# Zentrale.net
KiCad netlist of a schematic drawn in EAGLE
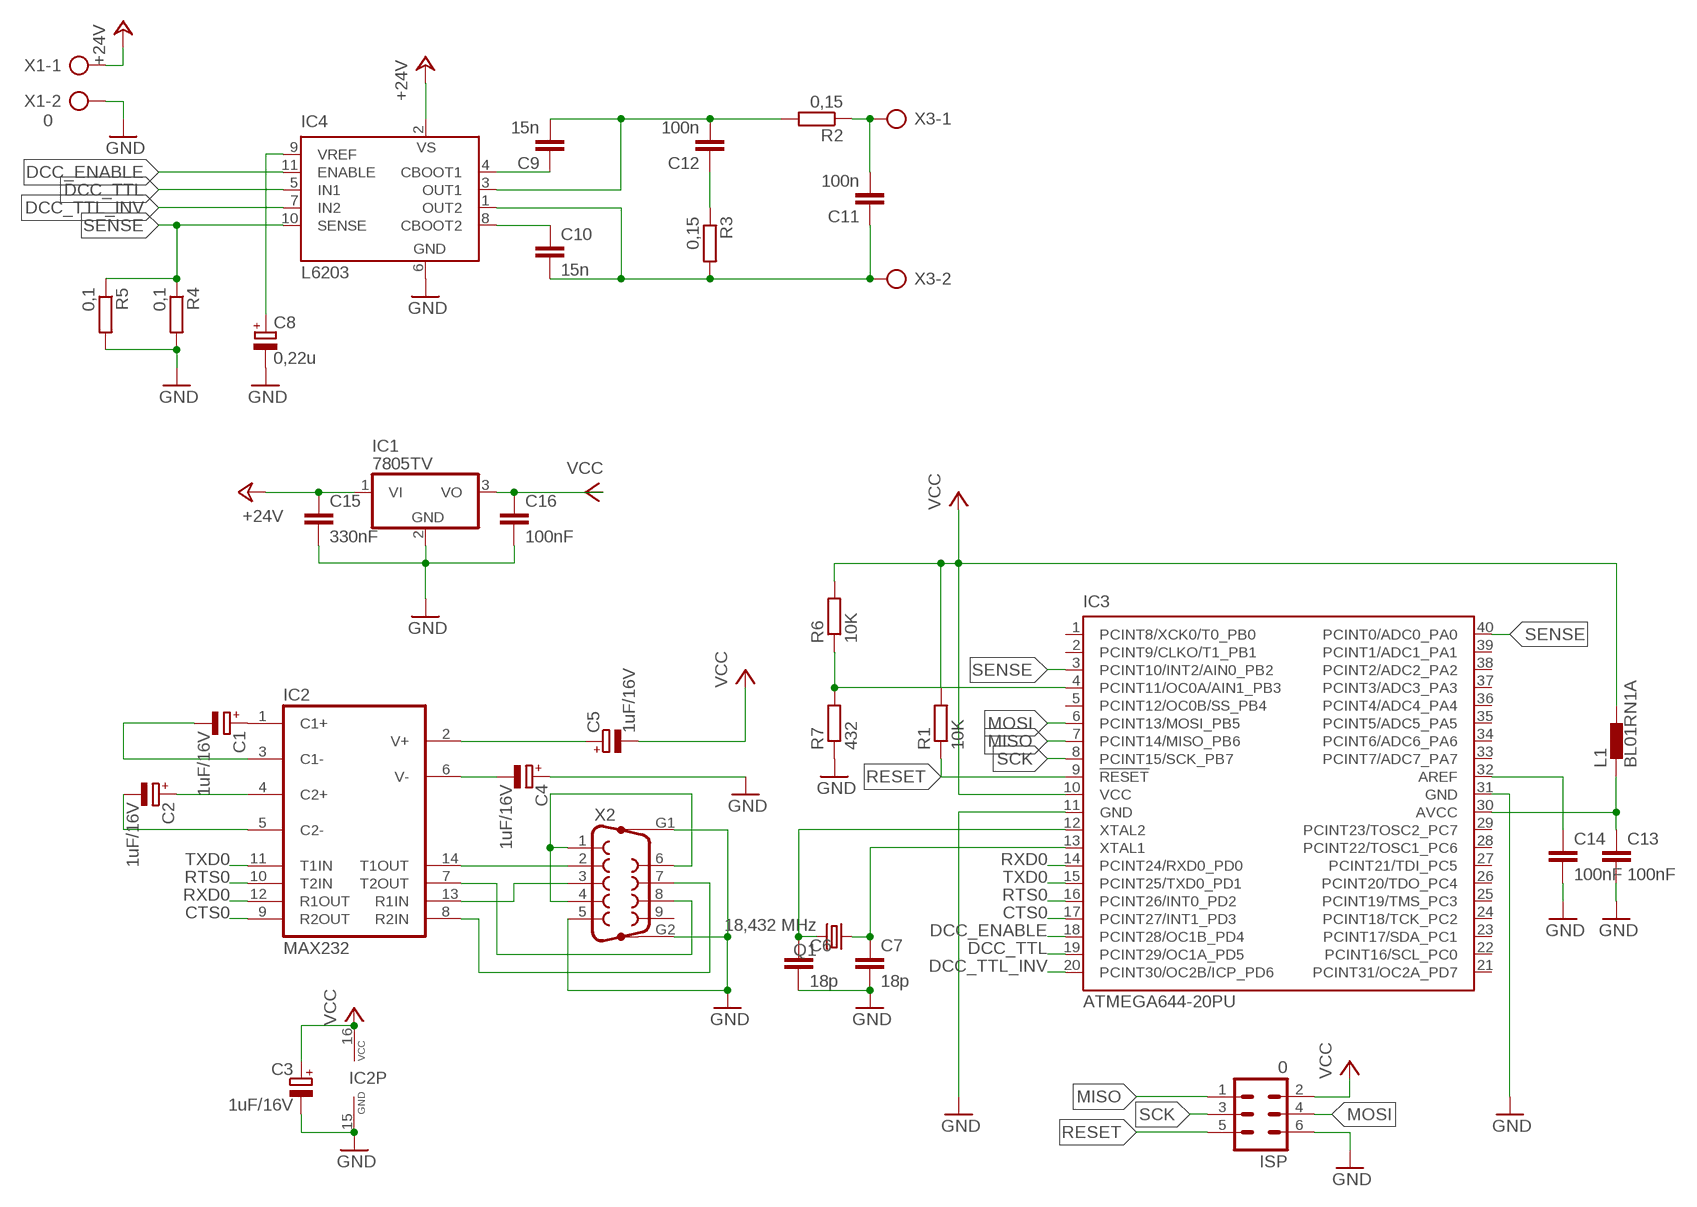
[diagram p0: schematic, sheet 1]

(export (version "E")
  (design (tool "Eeschema 10.0.6"))
  (components
    (comp (ref "C1")
      (value "1uF/16V")
      (footprint "eagle-import:TT2D5")
      (libsource (lib "eagle-import") (part "CPOL-EUTT2D5"))
    )
    (comp (ref "C2")
      (value "1uF/16V")
      (footprint "eagle-import:TT2D5")
      (libsource (lib "eagle-import") (part "CPOL-EUTT2D5"))
    )
    (comp (ref "C3")
      (value "1uF/16V")
      (footprint "eagle-import:TT2D5")
      (libsource (lib "eagle-import") (part "CPOL-EUTT2D5"))
    )
    (comp (ref "C4")
      (value "1uF/16V")
      (footprint "eagle-import:TT2D5")
      (libsource (lib "eagle-import") (part "CPOL-EUTT2D5"))
    )
    (comp (ref "C5")
      (value "1uF/16V")
      (footprint "eagle-import:TT2D5")
      (libsource (lib "eagle-import") (part "CPOL-EUTT2D5"))
    )
    (comp (ref "C6")
      (value "18p")
      (footprint "eagle-import:C025-025X050")
      (libsource (lib "eagle-import") (part "C-EU025-025X050"))
    )
    (comp (ref "C7")
      (value "18p")
      (footprint "eagle-import:C025-025X050")
      (libsource (lib "eagle-import") (part "C-EU025-025X050"))
    )
    (comp (ref "C8")
      (value "0,22u")
      (footprint "eagle-import:TT2D5")
      (libsource (lib "eagle-import") (part "CPOL-EUTT2D5"))
    )
    (comp (ref "C9")
      (value "15n")
      (footprint "eagle-import:C025-025X050")
      (libsource (lib "eagle-import") (part "C-EU025-025X050"))
    )
    (comp (ref "C10")
      (value "15n")
      (footprint "eagle-import:C025-025X050")
      (libsource (lib "eagle-import") (part "C-EU025-025X050"))
    )
    (comp (ref "C11")
      (value "100n")
      (footprint "eagle-import:C025-025X050")
      (libsource (lib "eagle-import") (part "C-EU025-025X050"))
    )
    (comp (ref "C12")
      (value "100n")
      (footprint "eagle-import:C025-025X050")
      (libsource (lib "eagle-import") (part "C-EU025-025X050"))
    )
    (comp (ref "C13")
      (value "100nF")
      (footprint "eagle-import:C025-025X050")
      (libsource (lib "eagle-import") (part "C-EU025-025X050"))
    )
    (comp (ref "C14")
      (value "100nF")
      (footprint "eagle-import:C025-025X050")
      (libsource (lib "eagle-import") (part "C-EU025-025X050"))
    )
    (comp (ref "C15")
      (value "330nF")
      (footprint "eagle-import:C025-025X050")
      (libsource (lib "eagle-import") (part "C-EU025-025X050"))
    )
    (comp (ref "C16")
      (value "100nF")
      (footprint "eagle-import:C025-025X050")
      (libsource (lib "eagle-import") (part "C-EU025-025X050"))
    )
    (comp (ref "IC1")
      (value "7805TV")
      (footprint "eagle-import:TO220V")
      (libsource (lib "eagle-import") (part "78TV05"))
    )
    (comp (ref "IC2")
      (value "MAX232")
      (footprint "eagle-import:DIL16")
      (fields (field (name "MF") "MAXIM") (field (name "MPN") "MAX232ACPE+"))
      (libsource (lib "eagle-import") (part "MAX232"))
    )
    (comp (ref "IC3")
      (value "ATMEGA644-20PU")
      (footprint "eagle-import:DIL40")
      (libsource (lib "eagle-import") (part "ATMEGA644-PU20"))
    )
    (comp (ref "IC4")
      (value "L6203")
      (footprint "eagle-import:MULTIWATT-11")
      (libsource (lib "eagle-import") (part "L6203"))
    )
    (comp (ref "ISP")
      (value "0")
      (footprint "eagle-import:ML6")
      (libsource (lib "eagle-import") (part "ML6"))
    )
    (comp (ref "L1")
      (value "BL01RN1A")
      (footprint "eagle-import:BL01RN1A")
      (libsource (lib "eagle-import") (part "BL01RN1A"))
    )
    (comp (ref "Q1")
      (value "18,432 MHz")
      (footprint "eagle-import:HC18U-V")
      (libsource (lib "eagle-import") (part "CRYSTALHC18U-V"))
    )
    (comp (ref "R1")
      (value "10K")
      (footprint "eagle-import:0204_5")
      (libsource (lib "eagle-import") (part "R-EU_0204/5"))
    )
    (comp (ref "R2")
      (value "0,15")
      (footprint "eagle-import:0204_5")
      (libsource (lib "eagle-import") (part "R-EU_0204/5"))
    )
    (comp (ref "R3")
      (value "0,15")
      (footprint "eagle-import:0204_5")
      (libsource (lib "eagle-import") (part "R-EU_0204/5"))
    )
    (comp (ref "R4")
      (value "0,1")
      (footprint "eagle-import:0204_5")
      (libsource (lib "eagle-import") (part "R-EU_0204/5"))
    )
    (comp (ref "R5")
      (value "0,1")
      (footprint "eagle-import:0204_5")
      (libsource (lib "eagle-import") (part "R-EU_0204/5"))
    )
    (comp (ref "R6")
      (value "10K")
      (footprint "eagle-import:0204_5")
      (libsource (lib "eagle-import") (part "R-EU_0204/5"))
    )
    (comp (ref "R7")
      (value "432")
      (footprint "eagle-import:0204_5")
      (libsource (lib "eagle-import") (part "R-EU_0204/5"))
    )
    (comp (ref "X1")
      (value "0")
      (footprint "eagle-import:AK500_2")
      (libsource (lib "eagle-import") (part "AK500/2"))
    )
    (comp (ref "X2")
      (value "F09HP")
      (footprint "eagle-import:F09HP")
      (libsource (lib "eagle-import") (part "F09HP"))
    )
    (comp (ref "X3")
      (value "AK500/2")
      (footprint "eagle-import:AK500_2")
      (libsource (lib "eagle-import") (part "AK500/2"))
    )
  )
  (nets
    (net (code "1") (name "+24V") (class "Default")
      (node (ref "C15") (pin "1") (pinfunction "1_1") (pintype "passive"))
      (node (ref "IC1") (pin "1") (pinfunction "VI_1") (pintype "input"))
      (node (ref "IC4") (pin "2") (pinfunction "VS_2") (pintype "power_in"))
      (node (ref "X1") (pin "1") (pinfunction "KL_1") (pintype "passive"))
    )
    (net (code "2") (name "/CTS0") (class "Default")
      (node (ref "IC2") (pin "9") (pinfunction "R2OUT_9") (pintype "output"))
      (node (ref "IC3") (pin "17") (pinfunction "PCINT27/INT1_PD3_17") (pintype "bidirectional"))
    )
    (net (code "3") (name "/RTS0") (class "Default")
      (node (ref "IC2") (pin "10") (pinfunction "T2IN_10") (pintype "input"))
      (node (ref "IC3") (pin "16") (pinfunction "PCINT26/INT0_PD2_16") (pintype "bidirectional"))
    )
    (net (code "4") (name "/RXD0") (class "Default")
      (node (ref "IC2") (pin "12") (pinfunction "R1OUT_12") (pintype "output"))
      (node (ref "IC3") (pin "14") (pinfunction "PCINT24/RXD0_PD0_14") (pintype "bidirectional"))
    )
    (net (code "5") (name "/TXD0") (class "Default")
      (node (ref "IC2") (pin "11") (pinfunction "T1IN_11") (pintype "input"))
      (node (ref "IC3") (pin "15") (pinfunction "PCINT25/TXD0_PD1_15") (pintype "bidirectional"))
    )
    (net (code "6") (name "DCC_ENABLE") (class "Default")
      (node (ref "IC3") (pin "18") (pinfunction "PCINT28/OC1B_PD4_18") (pintype "bidirectional"))
      (node (ref "IC4") (pin "11") (pinfunction "ENABLE_11") (pintype "input"))
    )
    (net (code "7") (name "DCC_TTL") (class "Default")
      (node (ref "IC3") (pin "19") (pinfunction "PCINT29/OC1A_PD5_19") (pintype "bidirectional"))
      (node (ref "IC4") (pin "5") (pinfunction "IN1_5") (pintype "input"))
    )
    (net (code "8") (name "DCC_TTL_INV") (class "Default")
      (node (ref "IC3") (pin "20") (pinfunction "PCINT30/OC2B/ICP_PD6_20") (pintype "bidirectional"))
      (node (ref "IC4") (pin "7") (pinfunction "IN2_7") (pintype "input"))
    )
    (net (code "9") (name "GND") (class "Default")
      (node (ref "C13") (pin "2") (pinfunction "2_2") (pintype "passive"))
      (node (ref "C14") (pin "2") (pinfunction "2_2") (pintype "passive"))
      (node (ref "C15") (pin "2") (pinfunction "2_2") (pintype "passive"))
      (node (ref "C16") (pin "2") (pinfunction "2_2") (pintype "passive"))
      (node (ref "C3") (pin "-") (pinfunction "-_-") (pintype "passive"))
      (node (ref "C4") (pin "+") (pinfunction "+_+") (pintype "passive"))
      (node (ref "C6") (pin "2") (pinfunction "2_2") (pintype "passive"))
      (node (ref "C7") (pin "2") (pinfunction "2_2") (pintype "passive"))
      (node (ref "C8") (pin "-") (pinfunction "-_-") (pintype "passive"))
      (node (ref "IC1") (pin "2") (pinfunction "GND_2") (pintype "passive"))
      (node (ref "IC2") (pin "15") (pinfunction "GND_15") (pintype "power_in"))
      (node (ref "IC3") (pin "11") (pinfunction "GND_11") (pintype "power_in"))
      (node (ref "IC3") (pin "31") (pinfunction "GND_31") (pintype "power_in"))
      (node (ref "IC4") (pin "6") (pinfunction "GND_6") (pintype "power_in"))
      (node (ref "ISP") (pin "6") (pinfunction "6_6") (pintype "passive"))
      (node (ref "R4") (pin "2") (pinfunction "2_2") (pintype "passive"))
      (node (ref "R5") (pin "2") (pinfunction "2_2") (pintype "passive"))
      (node (ref "R7") (pin "1") (pinfunction "1_1") (pintype "passive"))
      (node (ref "X1") (pin "2") (pinfunction "KL_2") (pintype "passive"))
      (node (ref "X2") (pin "5") (pinfunction "5_5") (pintype "passive"))
      (node (ref "X2") (pin "G1") (pinfunction "G1_G1") (pintype "passive"))
      (node (ref "X2") (pin "G2") (pinfunction "G2_G2") (pintype "passive"))
    )
    (net (code "10") (name "MISO") (class "Default")
      (node (ref "IC3") (pin "7") (pinfunction "PCINT14/MISO_PB6_7") (pintype "bidirectional"))
      (node (ref "ISP") (pin "1") (pinfunction "1_1") (pintype "passive"))
    )
    (net (code "11") (name "MOSI") (class "Default")
      (node (ref "IC3") (pin "6") (pinfunction "PCINT13/MOSI_PB5_6") (pintype "bidirectional"))
      (node (ref "ISP") (pin "4") (pinfunction "4_4") (pintype "passive"))
    )
    (net (code "12") (name "Net-(C12-Pad1)") (class "Default")
      (node (ref "C12") (pin "1") (pinfunction "1_1") (pintype "passive"))
      (node (ref "R3") (pin "1") (pinfunction "1_1") (pintype "passive"))
    )
    (net (code "13") (name "Net-(IC2A-C1+)") (class "Default")
      (node (ref "C1") (pin "+") (pinfunction "+_+") (pintype "passive"))
      (node (ref "IC2") (pin "1") (pinfunction "C1+_1") (pintype "bidirectional"))
    )
    (net (code "14") (name "Net-(IC2A-C1-)") (class "Default")
      (node (ref "C1") (pin "-") (pinfunction "-_-") (pintype "passive"))
      (node (ref "IC2") (pin "3") (pinfunction "C1-_3") (pintype "bidirectional"))
    )
    (net (code "15") (name "Net-(IC2A-C2+)") (class "Default")
      (node (ref "C2") (pin "+") (pinfunction "+_+") (pintype "passive"))
      (node (ref "IC2") (pin "4") (pinfunction "C2+_4") (pintype "bidirectional"))
    )
    (net (code "16") (name "Net-(IC2A-C2-)") (class "Default")
      (node (ref "C2") (pin "-") (pinfunction "-_-") (pintype "passive"))
      (node (ref "IC2") (pin "5") (pinfunction "C2-_5") (pintype "bidirectional"))
    )
    (net (code "17") (name "Net-(IC2A-R1IN)") (class "Default")
      (node (ref "IC2") (pin "13") (pinfunction "R1IN_13") (pintype "input"))
      (node (ref "X2") (pin "3") (pinfunction "3_3") (pintype "passive"))
    )
    (net (code "18") (name "Net-(IC2A-R2IN)") (class "Default")
      (node (ref "IC2") (pin "8") (pinfunction "R2IN_8") (pintype "input"))
      (node (ref "X2") (pin "7") (pinfunction "7_7") (pintype "passive"))
    )
    (net (code "19") (name "Net-(IC2A-T1OUT)") (class "Default")
      (node (ref "IC2") (pin "14") (pinfunction "T1OUT_14") (pintype "output"))
      (node (ref "X2") (pin "2") (pinfunction "2_2") (pintype "passive"))
    )
    (net (code "20") (name "Net-(IC2A-T2OUT)") (class "Default")
      (node (ref "IC2") (pin "7") (pinfunction "T2OUT_7") (pintype "output"))
      (node (ref "X2") (pin "8") (pinfunction "8_8") (pintype "passive"))
    )
    (net (code "21") (name "Net-(IC2A-V+)") (class "Default")
      (node (ref "C5") (pin "+") (pinfunction "+_+") (pintype "passive"))
      (node (ref "IC2") (pin "2") (pinfunction "V+_2") (pintype "bidirectional"))
    )
    (net (code "22") (name "Net-(IC2A-V-)") (class "Default")
      (node (ref "C4") (pin "-") (pinfunction "-_-") (pintype "passive"))
      (node (ref "IC2") (pin "6") (pinfunction "V-_6") (pintype "bidirectional"))
    )
    (net (code "23") (name "Net-(IC3-AREF)") (class "Default")
      (node (ref "C14") (pin "1") (pinfunction "1_1") (pintype "passive"))
      (node (ref "IC3") (pin "32") (pinfunction "AREF_32") (pintype "passive"))
    )
    (net (code "24") (name "Net-(IC3-AVCC)") (class "Default")
      (node (ref "C13") (pin "1") (pinfunction "1_1") (pintype "passive"))
      (node (ref "IC3") (pin "30") (pinfunction "AVCC_30") (pintype "power_in"))
      (node (ref "L1") (pin "1") (pinfunction "1_1") (pintype "passive"))
    )
    (net (code "25") (name "Net-(IC3-PCINT11{slash}OC0A{slash}AIN1_PB3)") (class "Default")
      (node (ref "IC3") (pin "4") (pinfunction "PCINT11/OC0A/AIN1_PB3_4") (pintype "bidirectional"))
      (node (ref "R6") (pin "1") (pinfunction "1_1") (pintype "passive"))
      (node (ref "R7") (pin "2") (pinfunction "2_2") (pintype "passive"))
    )
    (net (code "26") (name "Net-(IC3-XTAL1)") (class "Default")
      (node (ref "C7") (pin "1") (pinfunction "1_1") (pintype "passive"))
      (node (ref "IC3") (pin "13") (pinfunction "XTAL1_13") (pintype "input"))
      (node (ref "Q1") (pin "1") (pinfunction "1_1") (pintype "passive"))
    )
    (net (code "27") (name "Net-(IC3-XTAL2)") (class "Default")
      (node (ref "C6") (pin "1") (pinfunction "1_1") (pintype "passive"))
      (node (ref "IC3") (pin "12") (pinfunction "XTAL2_12") (pintype "output"))
      (node (ref "Q1") (pin "2") (pinfunction "2_2") (pintype "passive"))
    )
    (net (code "28") (name "Net-(IC4-CBOOT1)") (class "Default")
      (node (ref "C9") (pin "1") (pinfunction "1_1") (pintype "passive"))
      (node (ref "IC4") (pin "4") (pinfunction "CBOOT1_4") (pintype "input"))
    )
    (net (code "29") (name "Net-(IC4-CBOOT2)") (class "Default")
      (node (ref "C10") (pin "1") (pinfunction "1_1") (pintype "passive"))
      (node (ref "IC4") (pin "8") (pinfunction "CBOOT2_8") (pintype "input"))
    )
    (net (code "30") (name "Net-(IC4-OUT1)") (class "Default")
      (node (ref "C12") (pin "2") (pinfunction "2_2") (pintype "passive"))
      (node (ref "C9") (pin "2") (pinfunction "2_2") (pintype "passive"))
      (node (ref "IC4") (pin "3") (pinfunction "OUT1_3") (pintype "output"))
      (node (ref "R2") (pin "2") (pinfunction "2_2") (pintype "passive"))
    )
    (net (code "31") (name "Net-(IC4-OUT2)") (class "Default")
      (node (ref "C10") (pin "2") (pinfunction "2_2") (pintype "passive"))
      (node (ref "C11") (pin "1") (pinfunction "1_1") (pintype "passive"))
      (node (ref "IC4") (pin "1") (pinfunction "OUT2_1") (pintype "output"))
      (node (ref "R3") (pin "2") (pinfunction "2_2") (pintype "passive"))
      (node (ref "X3") (pin "2") (pinfunction "KL_2") (pintype "passive"))
    )
    (net (code "32") (name "Net-(IC4-VREF)") (class "Default")
      (node (ref "C8") (pin "+") (pinfunction "+_+") (pintype "passive"))
      (node (ref "IC4") (pin "9") (pinfunction "VREF_9") (pintype "input"))
    )
    (net (code "33") (name "Net-(X2-Pad1)") (class "Default")
      (node (ref "X2") (pin "1") (pinfunction "1_1") (pintype "passive"))
      (node (ref "X2") (pin "4") (pinfunction "4_4") (pintype "passive"))
      (node (ref "X2") (pin "6") (pinfunction "6_6") (pintype "passive"))
    )
    (net (code "34") (name "Net-(X3A-KL)") (class "Default")
      (node (ref "C11") (pin "2") (pinfunction "2_2") (pintype "passive"))
      (node (ref "R2") (pin "1") (pinfunction "1_1") (pintype "passive"))
      (node (ref "X3") (pin "1") (pinfunction "KL_1") (pintype "passive"))
    )
    (net (code "35") (name "RESET") (class "Default")
      (node (ref "IC3") (pin "9") (pinfunction "~{RESET}_9") (pintype "input"))
      (node (ref "ISP") (pin "5") (pinfunction "5_5") (pintype "passive"))
      (node (ref "R1") (pin "1") (pinfunction "1_1") (pintype "passive"))
    )
    (net (code "36") (name "SCK") (class "Default")
      (node (ref "IC3") (pin "8") (pinfunction "PCINT15/SCK_PB7_8") (pintype "bidirectional"))
      (node (ref "ISP") (pin "3") (pinfunction "3_3") (pintype "passive"))
    )
    (net (code "37") (name "SENSE") (class "Default")
      (node (ref "IC3") (pin "3") (pinfunction "PCINT10/INT2/AIN0_PB2_3") (pintype "bidirectional"))
      (node (ref "IC3") (pin "40") (pinfunction "PCINT0/ADC0_PA0_40") (pintype "bidirectional"))
      (node (ref "IC4") (pin "10") (pinfunction "SENSE_10") (pintype "input"))
      (node (ref "R4") (pin "1") (pinfunction "1_1") (pintype "passive"))
      (node (ref "R5") (pin "1") (pinfunction "1_1") (pintype "passive"))
    )
    (net (code "38") (name "VCC") (class "Default")
      (node (ref "C16") (pin "1") (pinfunction "1_1") (pintype "passive"))
      (node (ref "C3") (pin "+") (pinfunction "+_+") (pintype "passive"))
      (node (ref "C5") (pin "-") (pinfunction "-_-") (pintype "passive"))
      (node (ref "IC1") (pin "3") (pinfunction "VO_3") (pintype "passive"))
      (node (ref "IC2") (pin "16") (pinfunction "VCC_16") (pintype "power_in"))
      (node (ref "IC3") (pin "10") (pinfunction "VCC_10") (pintype "power_in"))
      (node (ref "ISP") (pin "2") (pinfunction "2_2") (pintype "passive"))
      (node (ref "L1") (pin "2") (pinfunction "2_2") (pintype "passive"))
      (node (ref "R1") (pin "2") (pinfunction "2_2") (pintype "passive"))
      (node (ref "R6") (pin "2") (pinfunction "2_2") (pintype "passive"))
    )
    (net (code "39") (name "unconnected-(IC3-PCINT1{slash}ADC1_PA1-Pad39)") (class "Default")
      (node (ref "IC3") (pin "39") (pinfunction "PCINT1/ADC1_PA1_39") (pintype "bidirectional"))
    )
    (net (code "40") (name "unconnected-(IC3-PCINT2{slash}ADC2_PA2-Pad38)") (class "Default")
      (node (ref "IC3") (pin "38") (pinfunction "PCINT2/ADC2_PA2_38") (pintype "bidirectional"))
    )
    (net (code "41") (name "unconnected-(IC3-PCINT3{slash}ADC3_PA3-Pad37)") (class "Default")
      (node (ref "IC3") (pin "37") (pinfunction "PCINT3/ADC3_PA3_37") (pintype "bidirectional"))
    )
    (net (code "42") (name "unconnected-(IC3-PCINT4{slash}ADC4_PA4-Pad36)") (class "Default")
      (node (ref "IC3") (pin "36") (pinfunction "PCINT4/ADC4_PA4_36") (pintype "bidirectional"))
    )
    (net (code "43") (name "unconnected-(IC3-PCINT5{slash}ADC5_PA5-Pad35)") (class "Default")
      (node (ref "IC3") (pin "35") (pinfunction "PCINT5/ADC5_PA5_35") (pintype "bidirectional"))
    )
    (net (code "44") (name "unconnected-(IC3-PCINT6{slash}ADC6_PA6-Pad34)") (class "Default")
      (node (ref "IC3") (pin "34") (pinfunction "PCINT6/ADC6_PA6_34") (pintype "bidirectional"))
    )
    (net (code "45") (name "unconnected-(IC3-PCINT7{slash}ADC7_PA7-Pad33)") (class "Default")
      (node (ref "IC3") (pin "33") (pinfunction "PCINT7/ADC7_PA7_33") (pintype "bidirectional"))
    )
    (net (code "46") (name "unconnected-(IC3-PCINT8{slash}XCK0{slash}T0_PB0-Pad1)") (class "Default")
      (node (ref "IC3") (pin "1") (pinfunction "PCINT8/XCK0/T0_PB0_1") (pintype "bidirectional"))
    )
    (net (code "47") (name "unconnected-(IC3-PCINT9{slash}CLKO{slash}T1_PB1-Pad2)") (class "Default")
      (node (ref "IC3") (pin "2") (pinfunction "PCINT9/CLKO/T1_PB1_2") (pintype "bidirectional"))
    )
    (net (code "48") (name "unconnected-(IC3-PCINT12{slash}OC0B{slash}SS_PB4-Pad5)") (class "Default")
      (node (ref "IC3") (pin "5") (pinfunction "PCINT12/OC0B/SS_PB4_5") (pintype "bidirectional"))
    )
    (net (code "49") (name "unconnected-(IC3-PCINT16{slash}SCL_PC0-Pad22)") (class "Default")
      (node (ref "IC3") (pin "22") (pinfunction "PCINT16/SCL_PC0_22") (pintype "bidirectional"))
    )
    (net (code "50") (name "unconnected-(IC3-PCINT17{slash}SDA_PC1-Pad23)") (class "Default")
      (node (ref "IC3") (pin "23") (pinfunction "PCINT17/SDA_PC1_23") (pintype "bidirectional"))
    )
    (net (code "51") (name "unconnected-(IC3-PCINT18{slash}TCK_PC2-Pad24)") (class "Default")
      (node (ref "IC3") (pin "24") (pinfunction "PCINT18/TCK_PC2_24") (pintype "bidirectional"))
    )
    (net (code "52") (name "unconnected-(IC3-PCINT19{slash}TMS_PC3-Pad25)") (class "Default")
      (node (ref "IC3") (pin "25") (pinfunction "PCINT19/TMS_PC3_25") (pintype "bidirectional"))
    )
    (net (code "53") (name "unconnected-(IC3-PCINT20{slash}TDO_PC4-Pad26)") (class "Default")
      (node (ref "IC3") (pin "26") (pinfunction "PCINT20/TDO_PC4_26") (pintype "bidirectional"))
    )
    (net (code "54") (name "unconnected-(IC3-PCINT21{slash}TDI_PC5-Pad27)") (class "Default")
      (node (ref "IC3") (pin "27") (pinfunction "PCINT21/TDI_PC5_27") (pintype "bidirectional"))
    )
    (net (code "55") (name "unconnected-(IC3-PCINT22{slash}TOSC1_PC6-Pad28)") (class "Default")
      (node (ref "IC3") (pin "28") (pinfunction "PCINT22/TOSC1_PC6_28") (pintype "bidirectional"))
    )
    (net (code "56") (name "unconnected-(IC3-PCINT23{slash}TOSC2_PC7-Pad29)") (class "Default")
      (node (ref "IC3") (pin "29") (pinfunction "PCINT23/TOSC2_PC7_29") (pintype "bidirectional"))
    )
    (net (code "57") (name "unconnected-(IC3-PCINT31{slash}OC2A_PD7-Pad21)") (class "Default")
      (node (ref "IC3") (pin "21") (pinfunction "PCINT31/OC2A_PD7_21") (pintype "bidirectional"))
    )
    (net (code "58") (name "unconnected-(X2-Pad9)") (class "Default")
      (node (ref "X2") (pin "9") (pinfunction "9_9") (pintype "passive"))
    )
  )
)
